# ENeoPI-Wireless_v31.net
KiCad netlist of a schematic drawn in EAGLE
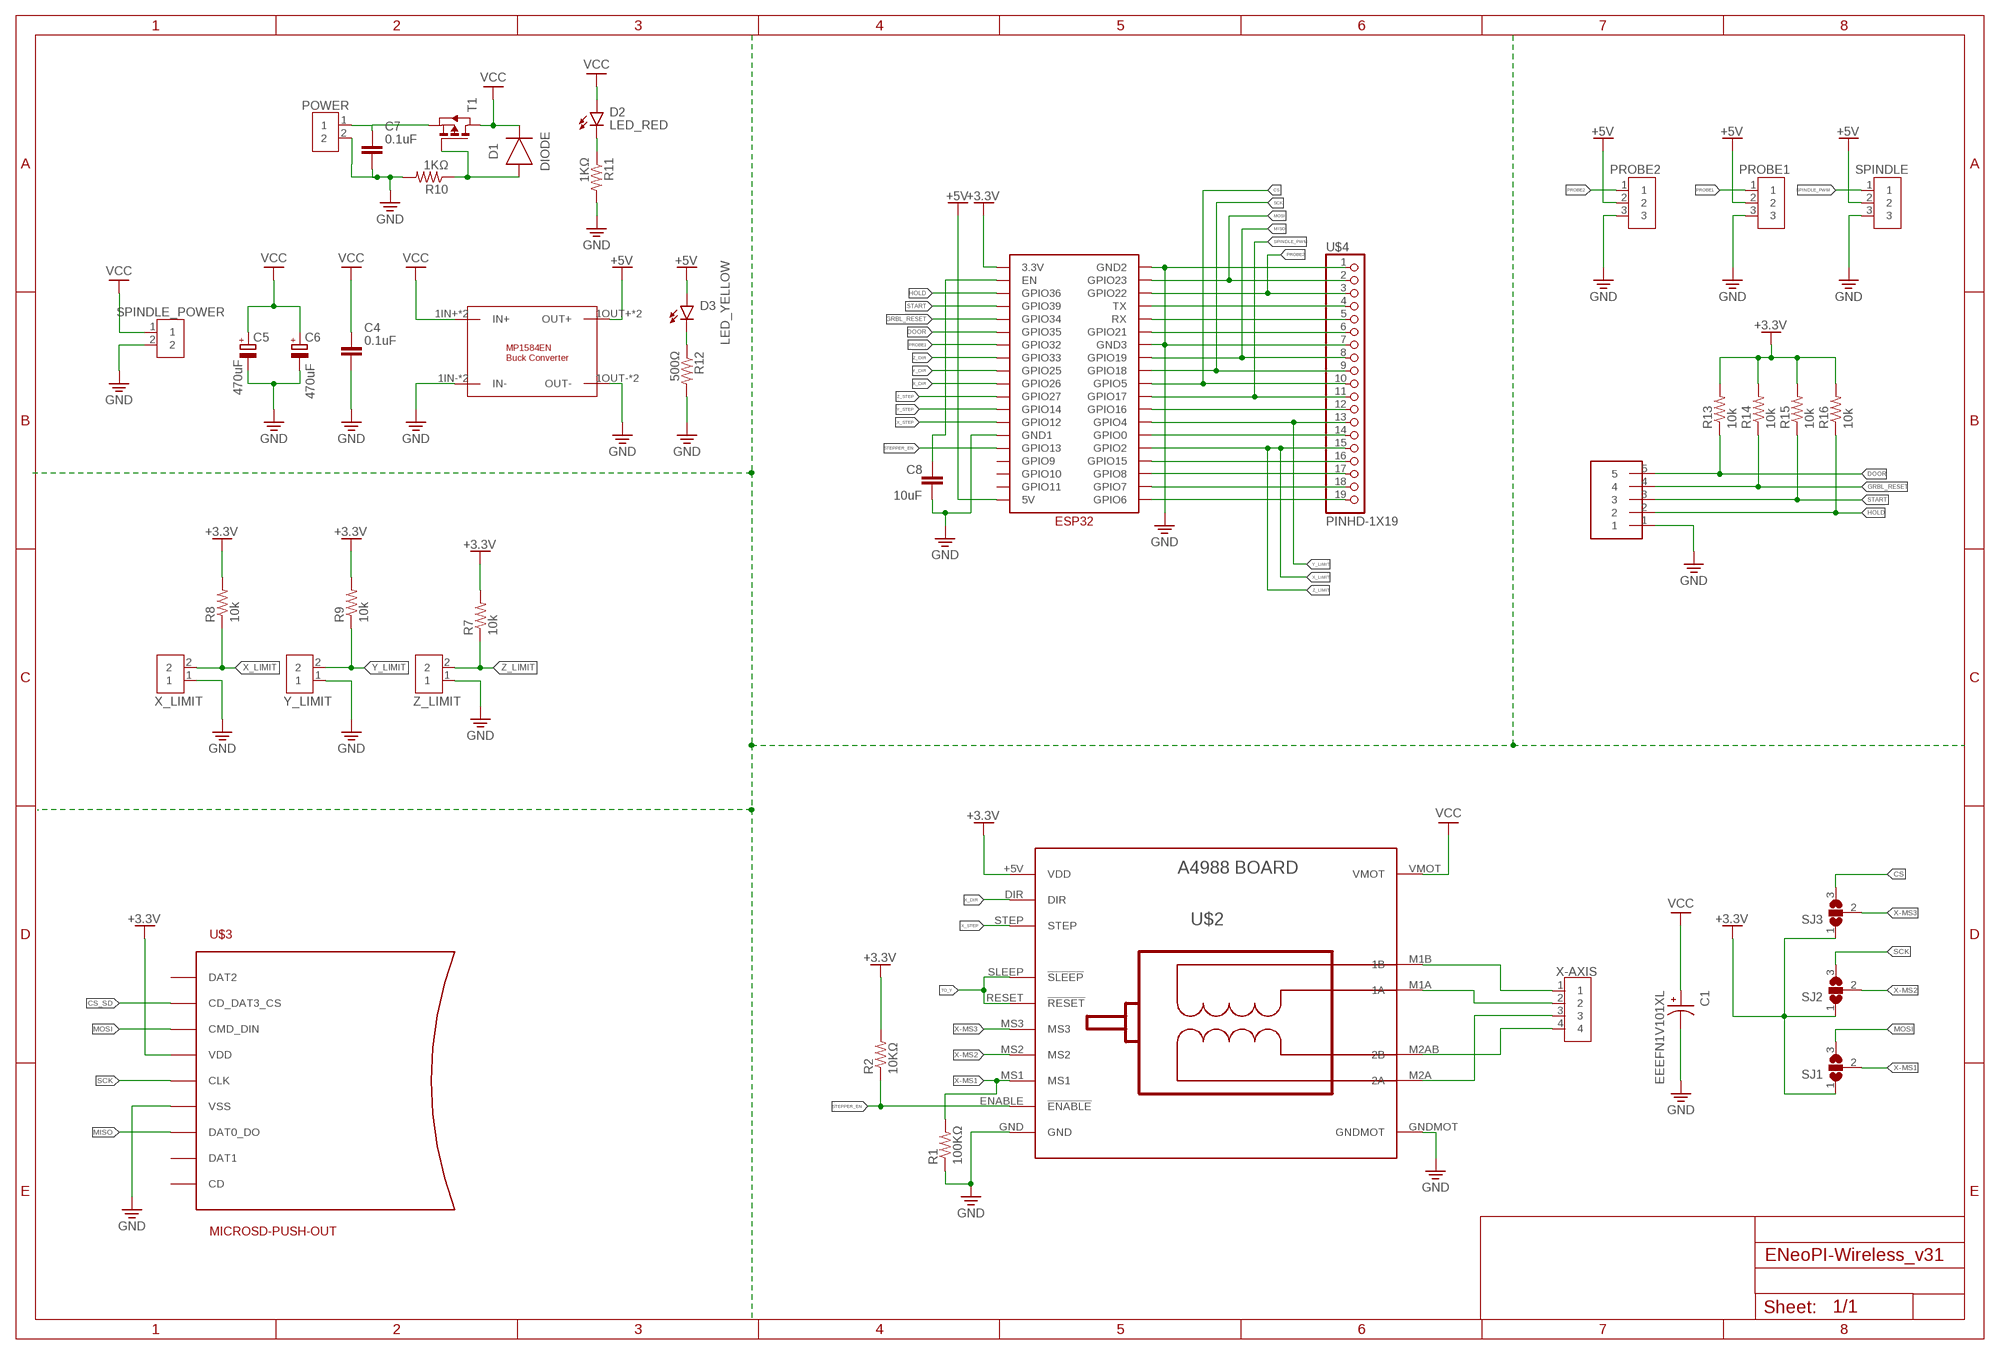
[diagram p0: schematic, sheet 1, part 1 of 2]
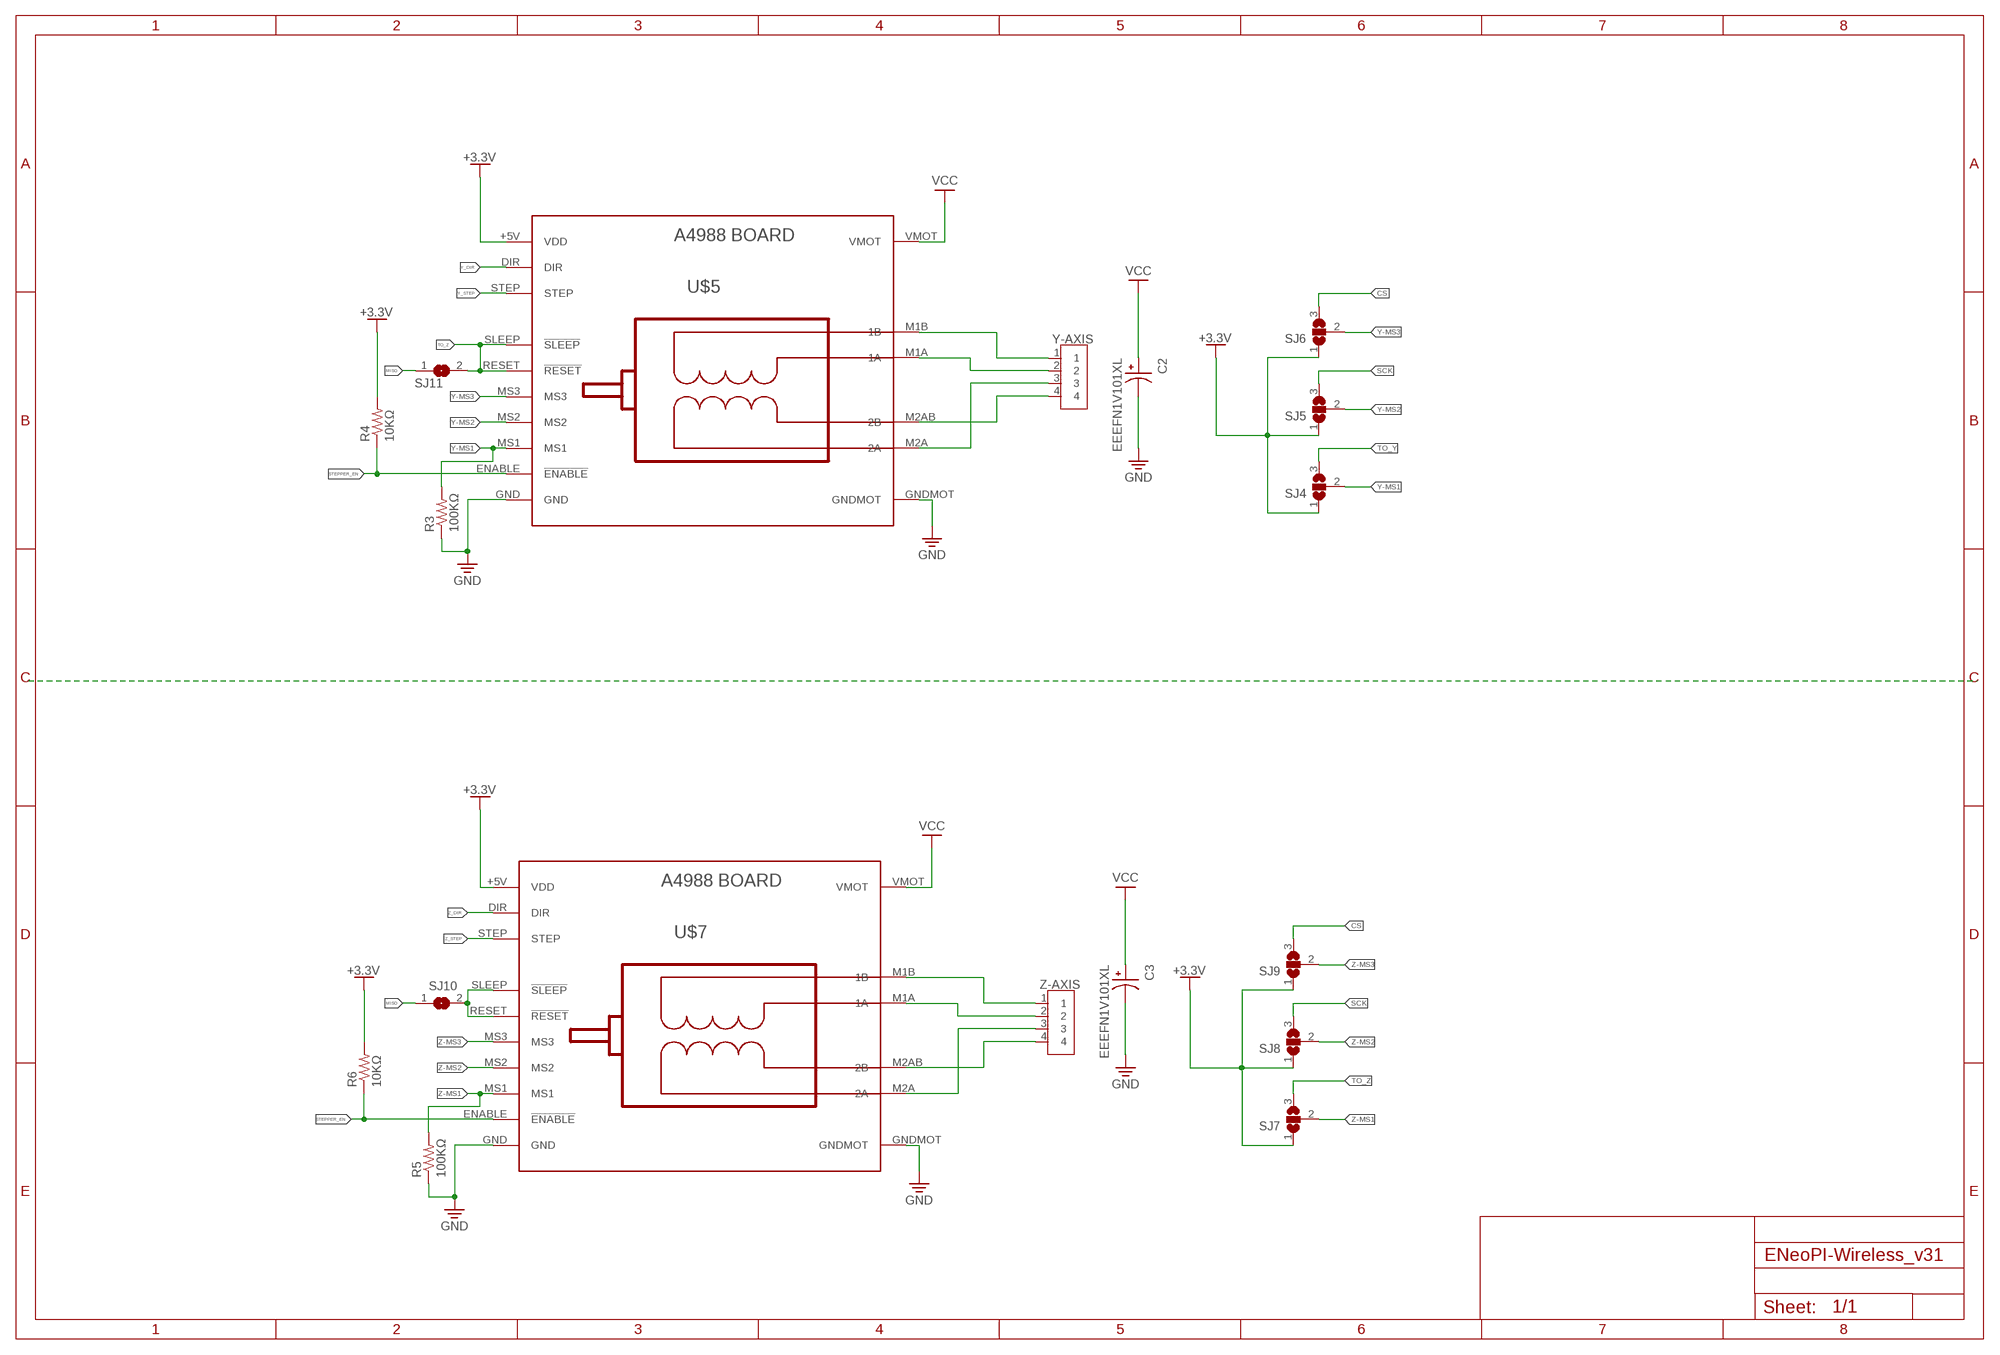
[diagram p1: schematic, sheet 1, part 2 of 2]

(export (version "E")
  (design (tool "Eeschema 10.0.6"))
  (components
    (comp (ref "C1")
      (value "EEEFN1V101XL")
      (footprint "eagle-import:CAP_EEEFN1V101XL")
      (fields (field (name "MANUFACTURER") "Panasonic"))
      (libsource (lib "eagle-import") (part "EEEFN1V101XL"))
    )
    (comp (ref "C2")
      (value "EEEFN1V101XL")
      (footprint "eagle-import:CAP_EEEFN1V101XL")
      (fields (field (name "MANUFACTURER") "Panasonic"))
      (libsource (lib "eagle-import") (part "EEEFN1V101XL"))
    )
    (comp (ref "C3")
      (value "EEEFN1V101XL")
      (footprint "eagle-import:CAP_EEEFN1V101XL")
      (fields (field (name "MANUFACTURER") "Panasonic"))
      (libsource (lib "eagle-import") (part "EEEFN1V101XL"))
    )
    (comp (ref "C4")
      (value "0.1uF")
      (footprint "eagle-import:CAPC3216X135")
      (libsource (lib "eagle-import") (part "CCHIP-1206(3216-METRIC)_"))
    )
    (comp (ref "C5")
      (value "470uF")
      (footprint "eagle-import:CAPAE1030X1050N")
      (libsource (lib "eagle-import") (part "C-POLECAP-10.5MM_"))
    )
    (comp (ref "C6")
      (value "470uF")
      (footprint "eagle-import:CAPAE1030X1050N")
      (libsource (lib "eagle-import") (part "C-POLECAP-10.5MM_"))
    )
    (comp (ref "C7")
      (value "0.1uF")
      (footprint "eagle-import:CAPC3216X135")
      (libsource (lib "eagle-import") (part "CCHIP-1206(3216-METRIC)_"))
    )
    (comp (ref "C8")
      (value "10uF")
      (footprint "eagle-import:CAPC3216X135")
      (libsource (lib "eagle-import") (part "CCHIP-1206(3216-METRIC)_"))
    )
    (comp (ref "D1")
      (value "DIODE")
      (footprint "eagle-import:DIOMELF5024")
      (libsource (lib "eagle-import") (part "DIODEDO-213AB(5025-METRIC)_"))
    )
    (comp (ref "D2")
      (value "LED_RED")
      (footprint "eagle-import:LEDC3216X75N_FLAT-R")
      (libsource (lib "eagle-import") (part "CHIP-FLAT-R_1206"))
    )
    (comp (ref "D3")
      (value "LED_YELLOW")
      (footprint "eagle-import:LEDC3216X75N_FLAT-Y")
      (libsource (lib "eagle-import") (part "CHIP-FLAT-Y_1206"))
    )
    (comp (ref "POWER")
      (value "2828XX-2282837-2")
      (footprint "eagle-import:TERMBLK_508-2N")
      (fields (field (name "MANUFACTURER") "TE Connectivity") (field (name "MPN") "282837-2"))
      (libsource (lib "eagle-import") (part "2828XX-2282837-2"))
    )
    (comp (ref "PROBE1")
      (value "2828XX-3282834-3")
      (footprint "eagle-import:TERMBLK_254-3N")
      (fields (field (name "MANUFACTURER") "TE Connectivity") (field (name "MPN") "282834-3"))
      (libsource (lib "eagle-import") (part "2828XX-3282834-3"))
    )
    (comp (ref "PROBE2")
      (value "2828XX-3282834-3")
      (footprint "eagle-import:TERMBLK_254-3N")
      (fields (field (name "MANUFACTURER") "TE Connectivity") (field (name "MPN") "282834-3"))
      (libsource (lib "eagle-import") (part "2828XX-3282834-3"))
    )
    (comp (ref "R1")
      (value "100KΩ")
      (footprint "eagle-import:R1206FAB")
      (libsource (lib "eagle-import") (part "RES-US1206FAB"))
    )
    (comp (ref "R2")
      (value "10KΩ")
      (footprint "eagle-import:R1206FAB")
      (libsource (lib "eagle-import") (part "RES-US1206FAB"))
    )
    (comp (ref "R3")
      (value "100KΩ")
      (footprint "eagle-import:R1206FAB")
      (libsource (lib "eagle-import") (part "RES-US1206FAB"))
    )
    (comp (ref "R4")
      (value "10KΩ")
      (footprint "eagle-import:R1206FAB")
      (libsource (lib "eagle-import") (part "RES-US1206FAB"))
    )
    (comp (ref "R5")
      (value "100KΩ")
      (footprint "eagle-import:R1206FAB")
      (libsource (lib "eagle-import") (part "RES-US1206FAB"))
    )
    (comp (ref "R6")
      (value "10KΩ")
      (footprint "eagle-import:R1206FAB")
      (libsource (lib "eagle-import") (part "RES-US1206FAB"))
    )
    (comp (ref "R7")
      (value "10k")
      (footprint "eagle-import:R1206FAB")
      (libsource (lib "eagle-import") (part "RES-US1206FAB"))
    )
    (comp (ref "R8")
      (value "10k")
      (footprint "eagle-import:R1206FAB")
      (libsource (lib "eagle-import") (part "RES-US1206FAB"))
    )
    (comp (ref "R9")
      (value "10k")
      (footprint "eagle-import:R1206FAB")
      (libsource (lib "eagle-import") (part "RES-US1206FAB"))
    )
    (comp (ref "R10")
      (value "1KΩ")
      (footprint "eagle-import:R1206FAB")
      (libsource (lib "eagle-import") (part "RES-US1206FAB"))
    )
    (comp (ref "R11")
      (value "1KΩ")
      (footprint "eagle-import:R1206FAB")
      (libsource (lib "eagle-import") (part "RES-US1206FAB"))
    )
    (comp (ref "R12")
      (value "500Ω")
      (footprint "eagle-import:R1206FAB")
      (libsource (lib "eagle-import") (part "RES-US1206FAB"))
    )
    (comp (ref "R13")
      (value "10k")
      (footprint "eagle-import:R1206FAB")
      (libsource (lib "eagle-import") (part "RES-US1206FAB"))
    )
    (comp (ref "R14")
      (value "10k")
      (footprint "eagle-import:R1206FAB")
      (libsource (lib "eagle-import") (part "RES-US1206FAB"))
    )
    (comp (ref "R15")
      (value "10k")
      (footprint "eagle-import:R1206FAB")
      (libsource (lib "eagle-import") (part "RES-US1206FAB"))
    )
    (comp (ref "R16")
      (value "10k")
      (footprint "eagle-import:R1206FAB")
      (libsource (lib "eagle-import") (part "RES-US1206FAB"))
    )
    (comp (ref "SJ1")
      (value "SJ2W")
      (footprint "eagle-import:SJ_2")
      (libsource (lib "eagle-import") (part "SJ2W"))
    )
    (comp (ref "SJ2")
      (value "SJ2W")
      (footprint "eagle-import:SJ_2")
      (libsource (lib "eagle-import") (part "SJ2W"))
    )
    (comp (ref "SJ3")
      (value "SJ2W")
      (footprint "eagle-import:SJ_2")
      (libsource (lib "eagle-import") (part "SJ2W"))
    )
    (comp (ref "SJ4")
      (value "SJ2W")
      (footprint "eagle-import:SJ_2")
      (libsource (lib "eagle-import") (part "SJ2W"))
    )
    (comp (ref "SJ5")
      (value "SJ2W")
      (footprint "eagle-import:SJ_2")
      (libsource (lib "eagle-import") (part "SJ2W"))
    )
    (comp (ref "SJ6")
      (value "SJ2W")
      (footprint "eagle-import:SJ_2")
      (libsource (lib "eagle-import") (part "SJ2W"))
    )
    (comp (ref "SJ7")
      (value "SJ2W")
      (footprint "eagle-import:SJ_2")
      (libsource (lib "eagle-import") (part "SJ2W"))
    )
    (comp (ref "SJ8")
      (value "SJ2W")
      (footprint "eagle-import:SJ_2")
      (libsource (lib "eagle-import") (part "SJ2W"))
    )
    (comp (ref "SJ9")
      (value "SJ2W")
      (footprint "eagle-import:SJ_2")
      (libsource (lib "eagle-import") (part "SJ2W"))
    )
    (comp (ref "SJ10")
      (value "SJ")
      (footprint "eagle-import:SJ")
      (libsource (lib "eagle-import") (part "SJ"))
    )
    (comp (ref "SJ11")
      (value "SJ")
      (footprint "eagle-import:SJ")
      (libsource (lib "eagle-import") (part "SJ"))
    )
    (comp (ref "SPINDLE")
      (value "2828XX-3282834-3")
      (footprint "eagle-import:TERMBLK_254-3N")
      (fields (field (name "MANUFACTURER") "TE Connectivity") (field (name "MPN") "282834-3"))
      (libsource (lib "eagle-import") (part "2828XX-3282834-3"))
    )
    (comp (ref "SPINDLE_POWER")
      (value "2828XX-2282837-2")
      (footprint "eagle-import:TERMBLK_508-2N")
      (fields (field (name "MANUFACTURER") "TE Connectivity") (field (name "MPN") "282837-2"))
      (libsource (lib "eagle-import") (part "2828XX-2282837-2"))
    )
    (comp (ref "T1")
      (value "PMOSFET")
      (footprint "eagle-import:TO252")
      (libsource (lib "eagle-import") (part "PMOSFET"))
    )
    (comp (ref "U$1")
      (value "ESP32_GRBL")
      (footprint "eagle-import:ESP32_GRBL")
      (libsource (lib "eagle-import") (part "ESP32_GRBL"))
    )
    (comp (ref "U$2")
      (value "BOARD_A4988")
      (footprint "eagle-import:BOARD_A4988")
      (libsource (lib "eagle-import") (part "BOARD_A4988"))
    )
    (comp (ref "U$3")
      (value "MICROSD-PUSH-OUT")
      (footprint "eagle-import:MICROSD-PUSH-OUT")
      (libsource (lib "eagle-import") (part "MICROSD-PUSH-OUT"))
    )
    (comp (ref "U$4")
      (value "PINHD-1X19")
      (footprint "eagle-import:1X19")
      (libsource (lib "eagle-import") (part "PINHD-1X19"))
    )
    (comp (ref "U$5")
      (value "BOARD_A4988")
      (footprint "eagle-import:BOARD_A4988")
      (libsource (lib "eagle-import") (part "BOARD_A4988"))
    )
    (comp (ref "U$6")
      (value "MINI-360_DC-TO-DC_BUCK_CONVERTER")
      (footprint "eagle-import:MINI_BUCK_CONVERTER")
      (libsource (lib "eagle-import") (part "MINI-360_DC-TO-DC_BUCK_CONVERTER"))
    )
    (comp (ref "U$7")
      (value "BOARD_A4988")
      (footprint "eagle-import:BOARD_A4988")
      (libsource (lib "eagle-import") (part "BOARD_A4988"))
    )
    (comp (ref "U$8")
      (value "1X05_SMD")
      (footprint "eagle-import:1X05_SMD")
      (libsource (lib "eagle-import") (part "1X05_SMD"))
    )
    (comp (ref "X-AXIS")
      (value "2828XX-4282837-4")
      (footprint "eagle-import:TERMBLK_508-4N")
      (fields (field (name "MANUFACTURER") "TE Connectivity") (field (name "MPN") "282837-4"))
      (libsource (lib "eagle-import") (part "2828XX-4282837-4"))
    )
    (comp (ref "X_LIMIT")
      (value "2828XX-2282834-2")
      (footprint "eagle-import:TERMBLK_254-2N")
      (libsource (lib "eagle-import") (part "2828XX-2282834-2"))
    )
    (comp (ref "Y-AXIS")
      (value "2828XX-4282837-4")
      (footprint "eagle-import:TERMBLK_508-4N")
      (fields (field (name "MANUFACTURER") "TE Connectivity") (field (name "MPN") "282837-4"))
      (libsource (lib "eagle-import") (part "2828XX-4282837-4"))
    )
    (comp (ref "Y_LIMIT")
      (value "2828XX-2282834-2")
      (footprint "eagle-import:TERMBLK_254-2N")
      (libsource (lib "eagle-import") (part "2828XX-2282834-2"))
    )
    (comp (ref "Z-AXIS")
      (value "2828XX-4282837-4")
      (footprint "eagle-import:TERMBLK_508-4N")
      (fields (field (name "MANUFACTURER") "TE Connectivity") (field (name "MPN") "282837-4"))
      (libsource (lib "eagle-import") (part "2828XX-4282837-4"))
    )
    (comp (ref "Z_LIMIT")
      (value "2828XX-2282834-2")
      (footprint "eagle-import:TERMBLK_254-2N")
      (libsource (lib "eagle-import") (part "2828XX-2282834-2"))
    )
  )
  (nets
    (net (code "1") (name "+3.3V") (class "Default")
      (node (ref "R13") (pin "2") (pinfunction "2_2") (pintype "passive"))
      (node (ref "R14") (pin "2") (pinfunction "2_2") (pintype "passive"))
      (node (ref "R15") (pin "2") (pinfunction "2_2") (pintype "passive"))
      (node (ref "R16") (pin "2") (pinfunction "2_2") (pintype "passive"))
      (node (ref "R2") (pin "2") (pinfunction "2_2") (pintype "passive"))
      (node (ref "R4") (pin "2") (pinfunction "2_2") (pintype "passive"))
      (node (ref "R6") (pin "2") (pinfunction "2_2") (pintype "passive"))
      (node (ref "R7") (pin "2") (pinfunction "2_2") (pintype "passive"))
      (node (ref "R8") (pin "2") (pinfunction "2_2") (pintype "passive"))
      (node (ref "R9") (pin "2") (pinfunction "2_2") (pintype "passive"))
      (node (ref "SJ1") (pin "1") (pinfunction "1_1") (pintype "passive"))
      (node (ref "SJ2") (pin "1") (pinfunction "1_1") (pintype "passive"))
      (node (ref "SJ3") (pin "1") (pinfunction "1_1") (pintype "passive"))
      (node (ref "SJ4") (pin "1") (pinfunction "1_1") (pintype "passive"))
      (node (ref "SJ5") (pin "1") (pinfunction "1_1") (pintype "passive"))
      (node (ref "SJ6") (pin "1") (pinfunction "1_1") (pintype "passive"))
      (node (ref "SJ7") (pin "1") (pinfunction "1_1") (pintype "passive"))
      (node (ref "SJ8") (pin "1") (pinfunction "1_1") (pintype "passive"))
      (node (ref "SJ9") (pin "1") (pinfunction "1_1") (pintype "passive"))
      (node (ref "U$1") (pin "3.3V") (pinfunction "3.3V_3.3V") (pintype "bidirectional"))
      (node (ref "U$2") (pin "+5V") (pinfunction "VDD_+5V") (pintype "power_in"))
      (node (ref "U$3") (pin "4") (pinfunction "VDD_4") (pintype "bidirectional"))
      (node (ref "U$5") (pin "+5V") (pinfunction "VDD_+5V") (pintype "power_in"))
      (node (ref "U$7") (pin "+5V") (pinfunction "VDD_+5V") (pintype "power_in"))
    )
    (net (code "2") (name "+5V") (class "Default")
      (node (ref "D3") (pin "A") (pinfunction "A_A") (pintype "passive"))
      (node (ref "PROBE1") (pin "2") (pinfunction "2_2") (pintype "bidirectional"))
      (node (ref "PROBE2") (pin "2") (pinfunction "2_2") (pintype "bidirectional"))
      (node (ref "SPINDLE") (pin "2") (pinfunction "2_2") (pintype "bidirectional"))
      (node (ref "U$1") (pin "5V") (pinfunction "5V_5V") (pintype "bidirectional"))
      (node (ref "U$6") (pin "1OUT+") (pinfunction "OUT+_1OUT+") (pintype "bidirectional"))
      (node (ref "U$6") (pin "2OUT+") (pinfunction "OUT+_2OUT+") (pintype "bidirectional"))
    )
    (net (code "3") (name "CS") (class "Default")
      (node (ref "SJ3") (pin "3") (pinfunction "3_3") (pintype "passive"))
      (node (ref "SJ6") (pin "3") (pinfunction "3_3") (pintype "passive"))
      (node (ref "SJ9") (pin "3") (pinfunction "3_3") (pintype "passive"))
      (node (ref "U$1") (pin "GPIO5") (pinfunction "GPIO5_GPIO5") (pintype "bidirectional"))
      (node (ref "U$4") (pin "10") (pinfunction "10_10") (pintype "passive"))
    )
    (net (code "4") (name "CS_SD") (class "Default")
      (node (ref "U$3") (pin "2") (pinfunction "CD_DAT3_CS_2") (pintype "bidirectional"))
    )
    (net (code "5") (name "DOOR") (class "Default")
      (node (ref "R13") (pin "1") (pinfunction "1_1") (pintype "passive"))
      (node (ref "U$1") (pin "GPIO35") (pinfunction "GPIO35_GPIO35") (pintype "bidirectional"))
      (node (ref "U$8") (pin "5") (pinfunction "5_5") (pintype "bidirectional"))
    )
    (net (code "6") (name "GND") (class "Default")
      (node (ref "C1") (pin "2") (pinfunction "2_2") (pintype "passive"))
      (node (ref "C2") (pin "2") (pinfunction "2_2") (pintype "passive"))
      (node (ref "C3") (pin "2") (pinfunction "2_2") (pintype "passive"))
      (node (ref "C4") (pin "2") (pinfunction "2_2") (pintype "passive"))
      (node (ref "C5") (pin "2") (pinfunction "-_2") (pintype "passive"))
      (node (ref "C6") (pin "2") (pinfunction "-_2") (pintype "passive"))
      (node (ref "C7") (pin "2") (pinfunction "2_2") (pintype "passive"))
      (node (ref "C8") (pin "2") (pinfunction "2_2") (pintype "passive"))
      (node (ref "POWER") (pin "2") (pinfunction "2_2") (pintype "bidirectional"))
      (node (ref "PROBE1") (pin "3") (pinfunction "3_3") (pintype "bidirectional"))
      (node (ref "PROBE2") (pin "3") (pinfunction "3_3") (pintype "bidirectional"))
      (node (ref "R1") (pin "1") (pinfunction "1_1") (pintype "passive"))
      (node (ref "R10") (pin "2") (pinfunction "2_2") (pintype "passive"))
      (node (ref "R11") (pin "2") (pinfunction "2_2") (pintype "passive"))
      (node (ref "R12") (pin "2") (pinfunction "2_2") (pintype "passive"))
      (node (ref "R3") (pin "1") (pinfunction "1_1") (pintype "passive"))
      (node (ref "R5") (pin "1") (pinfunction "1_1") (pintype "passive"))
      (node (ref "SPINDLE") (pin "3") (pinfunction "3_3") (pintype "bidirectional"))
      (node (ref "SPINDLE_POWER") (pin "2") (pinfunction "2_2") (pintype "bidirectional"))
      (node (ref "U$1") (pin "GND1") (pinfunction "GND1_GND1") (pintype "bidirectional"))
      (node (ref "U$1") (pin "GND2") (pinfunction "GND2_GND2") (pintype "bidirectional"))
      (node (ref "U$1") (pin "GND3") (pinfunction "GND3_GND3") (pintype "bidirectional"))
      (node (ref "U$2") (pin "GND") (pinfunction "GND_GND") (pintype "power_in"))
      (node (ref "U$2") (pin "GNDMOT") (pinfunction "GNDMOT_GNDMOT") (pintype "power_in"))
      (node (ref "U$3") (pin "6") (pinfunction "VSS_6") (pintype "bidirectional"))
      (node (ref "U$3") (pin "G1") (pinfunction "VSS_G1") (pintype "bidirectional"))
      (node (ref "U$3") (pin "G2") (pinfunction "VSS_G2") (pintype "bidirectional"))
      (node (ref "U$3") (pin "G3") (pinfunction "VSS_G3") (pintype "bidirectional"))
      (node (ref "U$3") (pin "G4") (pinfunction "VSS_G4") (pintype "bidirectional"))
      (node (ref "U$4") (pin "1") (pinfunction "1_1") (pintype "passive"))
      (node (ref "U$4") (pin "7") (pinfunction "7_7") (pintype "passive"))
      (node (ref "U$5") (pin "GND") (pinfunction "GND_GND") (pintype "power_in"))
      (node (ref "U$5") (pin "GNDMOT") (pinfunction "GNDMOT_GNDMOT") (pintype "power_in"))
      (node (ref "U$6") (pin "1IN-") (pinfunction "IN-_1IN-") (pintype "bidirectional"))
      (node (ref "U$6") (pin "1OUT-") (pinfunction "OUT-_1OUT-") (pintype "bidirectional"))
      (node (ref "U$6") (pin "2IN-") (pinfunction "IN-_2IN-") (pintype "bidirectional"))
      (node (ref "U$6") (pin "2OUT-") (pinfunction "OUT-_2OUT-") (pintype "bidirectional"))
      (node (ref "U$7") (pin "GND") (pinfunction "GND_GND") (pintype "power_in"))
      (node (ref "U$7") (pin "GNDMOT") (pinfunction "GNDMOT_GNDMOT") (pintype "power_in"))
      (node (ref "U$8") (pin "1") (pinfunction "1_1") (pintype "bidirectional"))
      (node (ref "X_LIMIT") (pin "1") (pinfunction "1_1") (pintype "bidirectional"))
      (node (ref "Y_LIMIT") (pin "1") (pinfunction "1_1") (pintype "bidirectional"))
      (node (ref "Z_LIMIT") (pin "1") (pinfunction "1_1") (pintype "bidirectional"))
    )
    (net (code "7") (name "GRBL_RESET") (class "Default")
      (node (ref "R14") (pin "1") (pinfunction "1_1") (pintype "passive"))
      (node (ref "U$1") (pin "GPIO34") (pinfunction "GPIO34_GPIO34") (pintype "bidirectional"))
      (node (ref "U$8") (pin "4") (pinfunction "4_4") (pintype "bidirectional"))
    )
    (net (code "8") (name "HOLD") (class "Default")
      (node (ref "R16") (pin "1") (pinfunction "1_1") (pintype "passive"))
      (node (ref "U$1") (pin "GPIO36") (pinfunction "GPIO36_GPIO36") (pintype "bidirectional"))
      (node (ref "U$8") (pin "2") (pinfunction "2_2") (pintype "bidirectional"))
    )
    (net (code "9") (name "MISO") (class "Default")
      (node (ref "SJ10") (pin "1") (pinfunction "1_1") (pintype "passive"))
      (node (ref "SJ11") (pin "1") (pinfunction "1_1") (pintype "passive"))
      (node (ref "U$1") (pin "GPIO19") (pinfunction "GPIO19_GPIO19") (pintype "bidirectional"))
      (node (ref "U$3") (pin "7") (pinfunction "DAT0_DO_7") (pintype "bidirectional"))
      (node (ref "U$4") (pin "8") (pinfunction "8_8") (pintype "passive"))
    )
    (net (code "10") (name "MOSI") (class "Default")
      (node (ref "SJ1") (pin "3") (pinfunction "3_3") (pintype "passive"))
      (node (ref "U$1") (pin "GPIO23") (pinfunction "GPIO23_GPIO23") (pintype "bidirectional"))
      (node (ref "U$3") (pin "3") (pinfunction "CMD_DIN_3") (pintype "bidirectional"))
      (node (ref "U$4") (pin "2") (pinfunction "2_2") (pintype "passive"))
    )
    (net (code "11") (name "Net-(C8-Pad1)") (class "Default")
      (node (ref "C8") (pin "1") (pinfunction "1_1") (pintype "passive"))
      (node (ref "U$1") (pin "EN") (pinfunction "EN_EN") (pintype "bidirectional"))
    )
    (net (code "12") (name "Net-(D1-A)") (class "Default")
      (node (ref "D1") (pin "2") (pinfunction "A_2") (pintype "passive"))
      (node (ref "R10") (pin "1") (pinfunction "1_1") (pintype "passive"))
      (node (ref "T1") (pin "1") (pinfunction "G_1") (pintype "passive"))
    )
    (net (code "13") (name "Net-(D2-PadC)") (class "Default")
      (node (ref "D2") (pin "C") (pinfunction "C_C") (pintype "passive"))
      (node (ref "R11") (pin "1") (pinfunction "1_1") (pintype "passive"))
    )
    (net (code "14") (name "Net-(D3-PadC)") (class "Default")
      (node (ref "D3") (pin "C") (pinfunction "C_C") (pintype "passive"))
      (node (ref "R12") (pin "1") (pinfunction "1_1") (pintype "passive"))
    )
    (net (code "15") (name "Net-(T1-S)") (class "Default")
      (node (ref "C7") (pin "1") (pinfunction "1_1") (pintype "passive"))
      (node (ref "POWER") (pin "1") (pinfunction "1_1") (pintype "bidirectional"))
      (node (ref "T1") (pin "2") (pinfunction "S_2") (pintype "passive"))
    )
    (net (code "16") (name "Net-(U$1-PadGPIO0)") (class "Default")
      (node (ref "U$1") (pin "GPIO0") (pinfunction "GPIO0_GPIO0") (pintype "bidirectional"))
      (node (ref "U$4") (pin "14") (pinfunction "14_14") (pintype "passive"))
    )
    (net (code "17") (name "Net-(U$1-PadGPIO6)") (class "Default")
      (node (ref "U$1") (pin "GPIO6") (pinfunction "GPIO6_GPIO6") (pintype "bidirectional"))
      (node (ref "U$4") (pin "19") (pinfunction "19_19") (pintype "passive"))
    )
    (net (code "18") (name "Net-(U$1-PadGPIO7)") (class "Default")
      (node (ref "U$1") (pin "GPIO7") (pinfunction "GPIO7_GPIO7") (pintype "bidirectional"))
      (node (ref "U$4") (pin "18") (pinfunction "18_18") (pintype "passive"))
    )
    (net (code "19") (name "Net-(U$1-PadGPIO8)") (class "Default")
      (node (ref "U$1") (pin "GPIO8") (pinfunction "GPIO8_GPIO8") (pintype "bidirectional"))
      (node (ref "U$4") (pin "17") (pinfunction "17_17") (pintype "passive"))
    )
    (net (code "20") (name "Net-(U$1-PadGPIO16)") (class "Default")
      (node (ref "U$1") (pin "GPIO16") (pinfunction "GPIO16_GPIO16") (pintype "bidirectional"))
      (node (ref "U$4") (pin "12") (pinfunction "12_12") (pintype "passive"))
    )
    (net (code "21") (name "Net-(U$1-PadGPIO21)") (class "Default")
      (node (ref "U$1") (pin "GPIO21") (pinfunction "GPIO21_GPIO21") (pintype "bidirectional"))
      (node (ref "U$4") (pin "6") (pinfunction "6_6") (pintype "passive"))
    )
    (net (code "22") (name "Net-(U$1-PadRX)") (class "Default")
      (node (ref "U$1") (pin "RX") (pinfunction "RX_RX") (pintype "bidirectional"))
      (node (ref "U$4") (pin "5") (pinfunction "5_5") (pintype "passive"))
    )
    (net (code "23") (name "Net-(U$1-PadTX)") (class "Default")
      (node (ref "U$1") (pin "TX") (pinfunction "TX_TX") (pintype "bidirectional"))
      (node (ref "U$4") (pin "4") (pinfunction "4_4") (pintype "passive"))
    )
    (net (code "24") (name "Net-(U$2-1A)") (class "Default")
      (node (ref "U$2") (pin "M1A") (pinfunction "1A_M1A") (pintype "output"))
      (node (ref "X-AXIS") (pin "2") (pinfunction "2_2") (pintype "bidirectional"))
    )
    (net (code "25") (name "Net-(U$2-1B)") (class "Default")
      (node (ref "U$2") (pin "M1B") (pinfunction "1B_M1B") (pintype "output"))
      (node (ref "X-AXIS") (pin "1") (pinfunction "1_1") (pintype "bidirectional"))
    )
    (net (code "26") (name "Net-(U$2-2A)") (class "Default")
      (node (ref "U$2") (pin "M2A") (pinfunction "2A_M2A") (pintype "output"))
      (node (ref "X-AXIS") (pin "3") (pinfunction "3_3") (pintype "bidirectional"))
    )
    (net (code "27") (name "Net-(U$2-2B)") (class "Default")
      (node (ref "U$2") (pin "M2AB") (pinfunction "2B_M2AB") (pintype "output"))
      (node (ref "X-AXIS") (pin "4") (pinfunction "4_4") (pintype "bidirectional"))
    )
    (net (code "28") (name "Net-(U$5-1A)") (class "Default")
      (node (ref "U$5") (pin "M1A") (pinfunction "1A_M1A") (pintype "output"))
      (node (ref "Y-AXIS") (pin "2") (pinfunction "2_2") (pintype "bidirectional"))
    )
    (net (code "29") (name "Net-(U$5-1B)") (class "Default")
      (node (ref "U$5") (pin "M1B") (pinfunction "1B_M1B") (pintype "output"))
      (node (ref "Y-AXIS") (pin "1") (pinfunction "1_1") (pintype "bidirectional"))
    )
    (net (code "30") (name "Net-(U$5-2A)") (class "Default")
      (node (ref "U$5") (pin "M2A") (pinfunction "2A_M2A") (pintype "output"))
      (node (ref "Y-AXIS") (pin "3") (pinfunction "3_3") (pintype "bidirectional"))
    )
    (net (code "31") (name "Net-(U$5-2B)") (class "Default")
      (node (ref "U$5") (pin "M2AB") (pinfunction "2B_M2AB") (pintype "output"))
      (node (ref "Y-AXIS") (pin "4") (pinfunction "4_4") (pintype "bidirectional"))
    )
    (net (code "32") (name "Net-(U$7-1A)") (class "Default")
      (node (ref "U$7") (pin "M1A") (pinfunction "1A_M1A") (pintype "output"))
      (node (ref "Z-AXIS") (pin "2") (pinfunction "2_2") (pintype "bidirectional"))
    )
    (net (code "33") (name "Net-(U$7-1B)") (class "Default")
      (node (ref "U$7") (pin "M1B") (pinfunction "1B_M1B") (pintype "output"))
      (node (ref "Z-AXIS") (pin "1") (pinfunction "1_1") (pintype "bidirectional"))
    )
    (net (code "34") (name "Net-(U$7-2A)") (class "Default")
      (node (ref "U$7") (pin "M2A") (pinfunction "2A_M2A") (pintype "output"))
      (node (ref "Z-AXIS") (pin "3") (pinfunction "3_3") (pintype "bidirectional"))
    )
    (net (code "35") (name "Net-(U$7-2B)") (class "Default")
      (node (ref "U$7") (pin "M2AB") (pinfunction "2B_M2AB") (pintype "output"))
      (node (ref "Z-AXIS") (pin "4") (pinfunction "4_4") (pintype "bidirectional"))
    )
    (net (code "36") (name "Net-(U$7-~{RESET})") (class "Default")
      (node (ref "SJ10") (pin "2") (pinfunction "2_2") (pintype "passive"))
      (node (ref "U$7") (pin "RESET") (pinfunction "~{RESET}_RESET") (pintype "input"))
      (node (ref "U$7") (pin "SLEEP") (pinfunction "~{SLEEP}_SLEEP") (pintype "input"))
    )
    (net (code "37") (name "PROBE1") (class "Default")
      (node (ref "PROBE1") (pin "1") (pinfunction "1_1") (pintype "bidirectional"))
      (node (ref "U$1") (pin "GPIO32") (pinfunction "GPIO32_GPIO32") (pintype "bidirectional"))
    )
    (net (code "38") (name "PROBE2") (class "Default")
      (node (ref "PROBE2") (pin "1") (pinfunction "1_1") (pintype "bidirectional"))
      (node (ref "U$1") (pin "GPIO22") (pinfunction "GPIO22_GPIO22") (pintype "bidirectional"))
      (node (ref "U$4") (pin "3") (pinfunction "3_3") (pintype "passive"))
    )
    (net (code "39") (name "SCK") (class "Default")
      (node (ref "SJ2") (pin "3") (pinfunction "3_3") (pintype "passive"))
      (node (ref "SJ5") (pin "3") (pinfunction "3_3") (pintype "passive"))
      (node (ref "SJ8") (pin "3") (pinfunction "3_3") (pintype "passive"))
      (node (ref "U$1") (pin "GPIO18") (pinfunction "GPIO18_GPIO18") (pintype "bidirectional"))
      (node (ref "U$3") (pin "5") (pinfunction "CLK_5") (pintype "bidirectional"))
      (node (ref "U$4") (pin "9") (pinfunction "9_9") (pintype "passive"))
    )
    (net (code "40") (name "SPINDLE_PWM") (class "Default")
      (node (ref "SPINDLE") (pin "1") (pinfunction "1_1") (pintype "bidirectional"))
      (node (ref "U$1") (pin "GPIO17") (pinfunction "GPIO17_GPIO17") (pintype "bidirectional"))
      (node (ref "U$4") (pin "11") (pinfunction "11_11") (pintype "passive"))
    )
    (net (code "41") (name "START") (class "Default")
      (node (ref "R15") (pin "1") (pinfunction "1_1") (pintype "passive"))
      (node (ref "U$1") (pin "GPIO39") (pinfunction "GPIO39_GPIO39") (pintype "bidirectional"))
      (node (ref "U$8") (pin "3") (pinfunction "3_3") (pintype "bidirectional"))
    )
    (net (code "42") (name "STEPPER_EN") (class "Default")
      (node (ref "R2") (pin "1") (pinfunction "1_1") (pintype "passive"))
      (node (ref "R4") (pin "1") (pinfunction "1_1") (pintype "passive"))
      (node (ref "R6") (pin "1") (pinfunction "1_1") (pintype "passive"))
      (node (ref "U$1") (pin "GPIO13") (pinfunction "GPIO13_GPIO13") (pintype "bidirectional"))
      (node (ref "U$2") (pin "ENABLE") (pinfunction "~{ENABLE}_ENABLE") (pintype "input"))
      (node (ref "U$5") (pin "ENABLE") (pinfunction "~{ENABLE}_ENABLE") (pintype "input"))
      (node (ref "U$7") (pin "ENABLE") (pinfunction "~{ENABLE}_ENABLE") (pintype "input"))
    )
    (net (code "43") (name "TO_Y") (class "Default")
      (node (ref "SJ4") (pin "3") (pinfunction "3_3") (pintype "passive"))
      (node (ref "U$2") (pin "RESET") (pinfunction "~{RESET}_RESET") (pintype "input"))
      (node (ref "U$2") (pin "SLEEP") (pinfunction "~{SLEEP}_SLEEP") (pintype "input"))
    )
    (net (code "44") (name "TO_Z") (class "Default")
      (node (ref "SJ11") (pin "2") (pinfunction "2_2") (pintype "passive"))
      (node (ref "SJ7") (pin "3") (pinfunction "3_3") (pintype "passive"))
      (node (ref "U$5") (pin "RESET") (pinfunction "~{RESET}_RESET") (pintype "input"))
      (node (ref "U$5") (pin "SLEEP") (pinfunction "~{SLEEP}_SLEEP") (pintype "input"))
    )
    (net (code "45") (name "VCC") (class "Default")
      (node (ref "C1") (pin "1") (pinfunction "1_1") (pintype "passive"))
      (node (ref "C2") (pin "1") (pinfunction "1_1") (pintype "passive"))
      (node (ref "C3") (pin "1") (pinfunction "1_1") (pintype "passive"))
      (node (ref "C4") (pin "1") (pinfunction "1_1") (pintype "passive"))
      (node (ref "C5") (pin "1") (pinfunction "+_1") (pintype "passive"))
      (node (ref "C6") (pin "1") (pinfunction "+_1") (pintype "passive"))
      (node (ref "D1") (pin "1") (pinfunction "C_1") (pintype "passive"))
      (node (ref "D2") (pin "A") (pinfunction "A_A") (pintype "passive"))
      (node (ref "SPINDLE_POWER") (pin "1") (pinfunction "1_1") (pintype "bidirectional"))
      (node (ref "T1") (pin "3") (pinfunction "D_3") (pintype "passive"))
      (node (ref "U$2") (pin "VMOT") (pinfunction "VMOT_VMOT") (pintype "power_in"))
      (node (ref "U$5") (pin "VMOT") (pinfunction "VMOT_VMOT") (pintype "power_in"))
      (node (ref "U$6") (pin "1IN+") (pinfunction "IN+_1IN+") (pintype "bidirectional"))
      (node (ref "U$6") (pin "2IN+") (pinfunction "IN+_2IN+") (pintype "bidirectional"))
      (node (ref "U$7") (pin "VMOT") (pinfunction "VMOT_VMOT") (pintype "power_in"))
    )
    (net (code "46") (name "X-MS1") (class "Default")
      (node (ref "R1") (pin "2") (pinfunction "2_2") (pintype "passive"))
      (node (ref "SJ1") (pin "2") (pinfunction "2_2") (pintype "passive"))
      (node (ref "U$2") (pin "MS1") (pinfunction "MS1_MS1") (pintype "input"))
    )
    (net (code "47") (name "X-MS2") (class "Default")
      (node (ref "SJ2") (pin "2") (pinfunction "2_2") (pintype "passive"))
      (node (ref "U$2") (pin "MS2") (pinfunction "MS2_MS2") (pintype "input"))
    )
    (net (code "48") (name "X-MS3") (class "Default")
      (node (ref "SJ3") (pin "2") (pinfunction "2_2") (pintype "passive"))
      (node (ref "U$2") (pin "MS3") (pinfunction "MS3_MS3") (pintype "input"))
    )
    (net (code "49") (name "X_DIR") (class "Default")
      (node (ref "U$1") (pin "GPIO26") (pinfunction "GPIO26_GPIO26") (pintype "bidirectional"))
      (node (ref "U$2") (pin "DIR") (pinfunction "DIR_DIR") (pintype "input"))
    )
    (net (code "50") (name "X_LIMIT") (class "Default")
      (node (ref "R8") (pin "1") (pinfunction "1_1") (pintype "passive"))
      (node (ref "U$1") (pin "GPIO2") (pinfunction "GPIO2_GPIO2") (pintype "bidirectional"))
      (node (ref "U$4") (pin "15") (pinfunction "15_15") (pintype "passive"))
      (node (ref "X_LIMIT") (pin "2") (pinfunction "2_2") (pintype "bidirectional"))
    )
    (net (code "51") (name "X_STEP") (class "Default")
      (node (ref "U$1") (pin "GPIO12") (pinfunction "GPIO12_GPIO12") (pintype "bidirectional"))
      (node (ref "U$2") (pin "STEP") (pinfunction "STEP_STEP") (pintype "input"))
    )
    (net (code "52") (name "Y-MS1") (class "Default")
      (node (ref "R3") (pin "2") (pinfunction "2_2") (pintype "passive"))
      (node (ref "SJ4") (pin "2") (pinfunction "2_2") (pintype "passive"))
      (node (ref "U$5") (pin "MS1") (pinfunction "MS1_MS1") (pintype "input"))
    )
    (net (code "53") (name "Y-MS2") (class "Default")
      (node (ref "SJ5") (pin "2") (pinfunction "2_2") (pintype "passive"))
      (node (ref "U$5") (pin "MS2") (pinfunction "MS2_MS2") (pintype "input"))
    )
    (net (code "54") (name "Y-MS3") (class "Default")
      (node (ref "SJ6") (pin "2") (pinfunction "2_2") (pintype "passive"))
      (node (ref "U$5") (pin "MS3") (pinfunction "MS3_MS3") (pintype "input"))
    )
    (net (code "55") (name "Y_DIR") (class "Default")
      (node (ref "U$1") (pin "GPIO25") (pinfunction "GPIO25_GPIO25") (pintype "bidirectional"))
      (node (ref "U$5") (pin "DIR") (pinfunction "DIR_DIR") (pintype "input"))
    )
    (net (code "56") (name "Y_LIMIT") (class "Default")
      (node (ref "R9") (pin "1") (pinfunction "1_1") (pintype "passive"))
      (node (ref "U$1") (pin "GPIO4") (pinfunction "GPIO4_GPIO4") (pintype "bidirectional"))
      (node (ref "U$4") (pin "13") (pinfunction "13_13") (pintype "passive"))
      (node (ref "Y_LIMIT") (pin "2") (pinfunction "2_2") (pintype "bidirectional"))
    )
    (net (code "57") (name "Y_STEP") (class "Default")
      (node (ref "U$1") (pin "GPIO14") (pinfunction "GPIO14_GPIO14") (pintype "bidirectional"))
      (node (ref "U$5") (pin "STEP") (pinfunction "STEP_STEP") (pintype "input"))
    )
    (net (code "58") (name "Z-MS1") (class "Default")
      (node (ref "R5") (pin "2") (pinfunction "2_2") (pintype "passive"))
      (node (ref "SJ7") (pin "2") (pinfunction "2_2") (pintype "passive"))
      (node (ref "U$7") (pin "MS1") (pinfunction "MS1_MS1") (pintype "input"))
    )
    (net (code "59") (name "Z-MS2") (class "Default")
      (node (ref "SJ8") (pin "2") (pinfunction "2_2") (pintype "passive"))
      (node (ref "U$7") (pin "MS2") (pinfunction "MS2_MS2") (pintype "input"))
    )
    (net (code "60") (name "Z-MS3") (class "Default")
      (node (ref "SJ9") (pin "2") (pinfunction "2_2") (pintype "passive"))
      (node (ref "U$7") (pin "MS3") (pinfunction "MS3_MS3") (pintype "input"))
    )
    (net (code "61") (name "Z_DIR") (class "Default")
      (node (ref "U$1") (pin "GPIO33") (pinfunction "GPIO33_GPIO33") (pintype "bidirectional"))
      (node (ref "U$7") (pin "DIR") (pinfunction "DIR_DIR") (pintype "input"))
    )
    (net (code "62") (name "Z_LIMIT") (class "Default")
      (node (ref "R7") (pin "1") (pinfunction "1_1") (pintype "passive"))
      (node (ref "U$1") (pin "GPIO15") (pinfunction "GPIO15_GPIO15") (pintype "bidirectional"))
      (node (ref "U$4") (pin "16") (pinfunction "16_16") (pintype "passive"))
      (node (ref "Z_LIMIT") (pin "2") (pinfunction "2_2") (pintype "bidirectional"))
    )
    (net (code "63") (name "Z_STEP") (class "Default")
      (node (ref "U$1") (pin "GPIO27") (pinfunction "GPIO27_GPIO27") (pintype "bidirectional"))
      (node (ref "U$7") (pin "STEP") (pinfunction "STEP_STEP") (pintype "input"))
    )
    (net (code "64") (name "unconnected-(U$1-PadGPIO9)") (class "Default")
      (node (ref "U$1") (pin "GPIO9") (pinfunction "GPIO9_GPIO9") (pintype "bidirectional"))
    )
    (net (code "65") (name "unconnected-(U$1-PadGPIO10)") (class "Default")
      (node (ref "U$1") (pin "GPIO10") (pinfunction "GPIO10_GPIO10") (pintype "bidirectional"))
    )
    (net (code "66") (name "unconnected-(U$1-PadGPIO11)") (class "Default")
      (node (ref "U$1") (pin "GPIO11") (pinfunction "GPIO11_GPIO11") (pintype "bidirectional"))
    )
    (net (code "67") (name "unconnected-(U$3-DAT1-Pad8)") (class "Default")
      (node (ref "U$3") (pin "8") (pinfunction "DAT1_8") (pintype "bidirectional"))
    )
    (net (code "68") (name "unconnected-(U$3-DAT2-Pad1)") (class "Default")
      (node (ref "U$3") (pin "1") (pinfunction "DAT2_1") (pintype "bidirectional"))
    )
    (net (code "69") (name "unconnected-(U$3-PadCD)") (class "Default")
      (node (ref "U$3") (pin "CD") (pinfunction "CD_CD") (pintype "bidirectional"))
    )
  )
)
